# SCH.net
KiCad netlist of a schematic drawn in Altium Designer
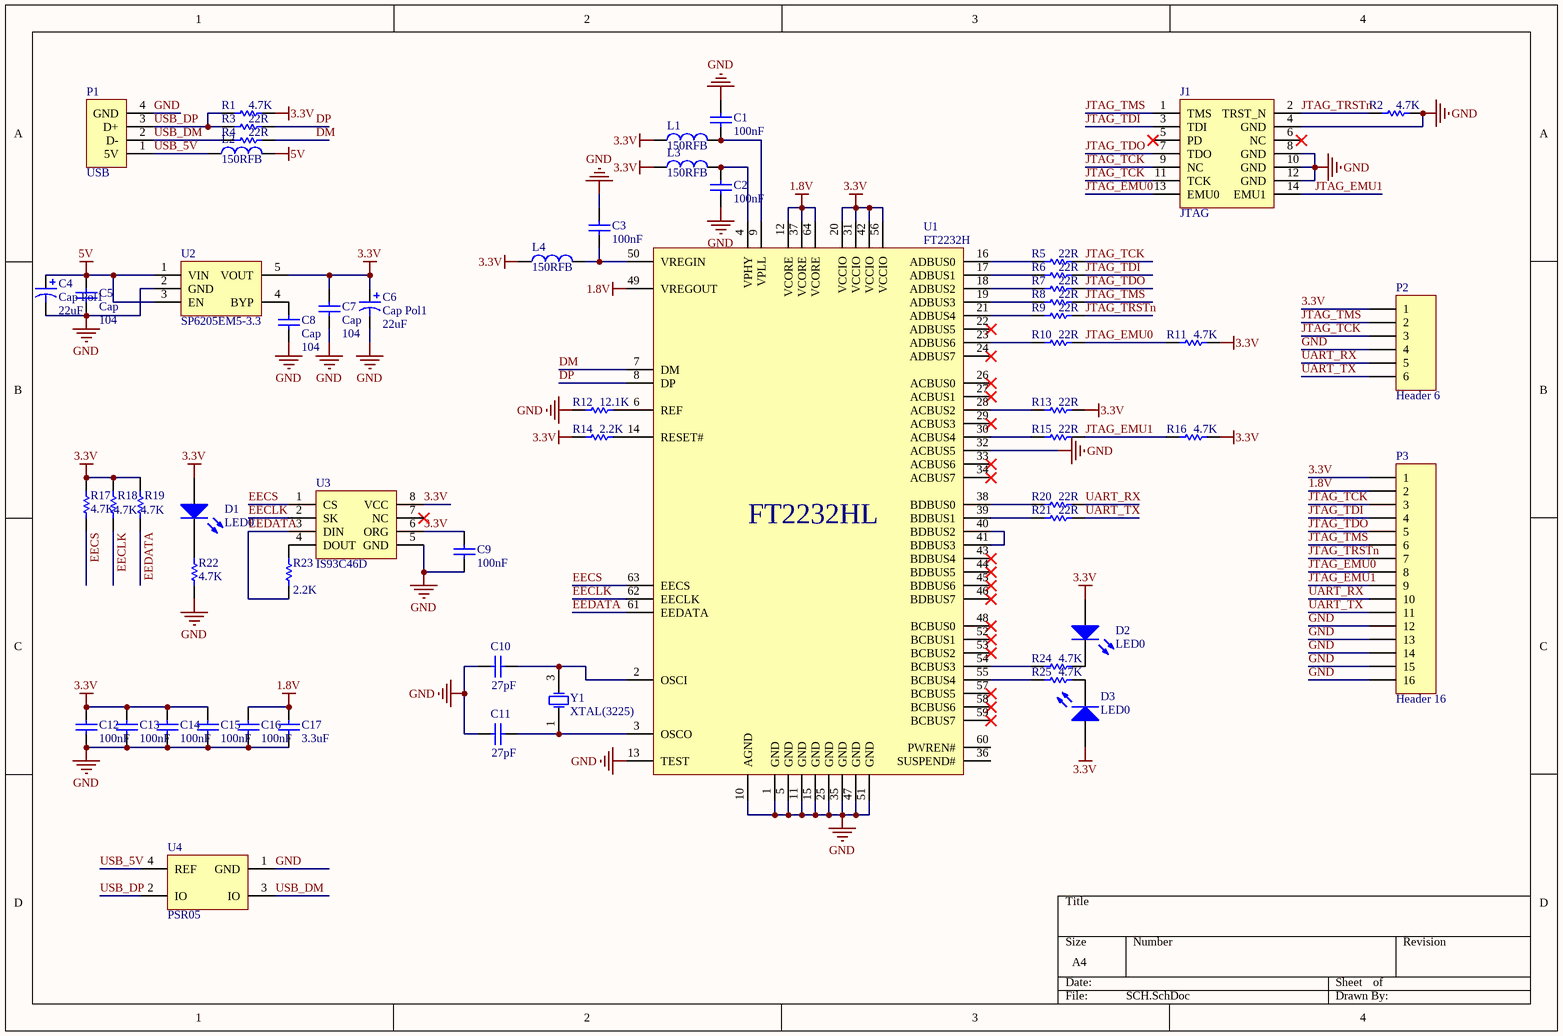
[diagram p0: SCH.SchDoc]

(export (version "E")
  (design (tool "Eeschema 10.0.6"))
  (components
    (comp (ref "C1")
      (value "100nF")
      (footprint "C0603")
      (description "Capacitor")
      (fields (field (name "Comment") "Cap") (field (name "PUBLISHER") "Altium Limited"))
      (libsource (lib "Miscellaneous Devices") (part "Cap"))
    )
    (comp (ref "C2")
      (value "100nF")
      (footprint "C0603")
      (description "Capacitor")
      (fields (field (name "Comment") "Cap") (field (name "PUBLISHER") "Altium Limited"))
      (libsource (lib "Miscellaneous Devices") (part "Cap"))
    )
    (comp (ref "C3")
      (value "100nF")
      (footprint "C0603")
      (description "Capacitor")
      (fields (field (name "Comment") "Cap") (field (name "PUBLISHER") "Altium Limited"))
      (libsource (lib "Miscellaneous Devices") (part "Cap"))
    )
    (comp (ref "C4")
      (value "Cap Pol1")
      (footprint "C0805")
      (description "Polarized Capacitor (Radial)")
      (fields (field (name "ALTIUM_VALUE") "22uF") (field (name "PUBLISHER") "Altium Limited"))
      (libsource (lib "Miscellaneous Devices") (part "Cap Pol1"))
    )
    (comp (ref "C5")
      (value "Cap")
      (footprint "C0603")
      (description "Capacitor")
      (fields (field (name "ALTIUM_VALUE") "104") (field (name "PUBLISHER") "Altium Limited"))
      (libsource (lib "Miscellaneous Devices") (part "Cap"))
    )
    (comp (ref "C6")
      (value "Cap Pol1")
      (footprint "C0805")
      (description "Polarized Capacitor (Radial)")
      (fields (field (name "ALTIUM_VALUE") "22uF") (field (name "PUBLISHER") "Altium Limited"))
      (libsource (lib "Miscellaneous Devices") (part "Cap Pol1"))
    )
    (comp (ref "C7")
      (value "Cap")
      (footprint "C0603")
      (description "Capacitor")
      (fields (field (name "ALTIUM_VALUE") "104") (field (name "PUBLISHER") "Altium Limited"))
      (libsource (lib "Miscellaneous Devices") (part "Cap"))
    )
    (comp (ref "C8")
      (value "Cap")
      (footprint "C0603")
      (description "Capacitor")
      (fields (field (name "ALTIUM_VALUE") "104") (field (name "PUBLISHER") "Altium Limited"))
      (libsource (lib "Miscellaneous Devices") (part "Cap"))
    )
    (comp (ref "C9")
      (value "100nF")
      (footprint "C0603")
      (description "Capacitor")
      (fields (field (name "Comment") "Cap") (field (name "PUBLISHER") "Altium Limited"))
      (libsource (lib "Miscellaneous Devices") (part "Cap"))
    )
    (comp (ref "C10")
      (value "27pF")
      (footprint "C0603")
      (description "Capacitor")
      (fields (field (name "Comment") "Cap") (field (name "PUBLISHER") "Altium Limited"))
      (libsource (lib "Miscellaneous Devices") (part "Cap"))
    )
    (comp (ref "C11")
      (value "27pF")
      (footprint "C0603")
      (description "Capacitor")
      (fields (field (name "Comment") "Cap") (field (name "PUBLISHER") "Altium Limited"))
      (libsource (lib "Miscellaneous Devices") (part "Cap"))
    )
    (comp (ref "C12")
      (value "100nF")
      (footprint "C0603")
      (description "Capacitor")
      (fields (field (name "Comment") "Cap") (field (name "PUBLISHER") "Altium Limited"))
      (libsource (lib "Miscellaneous Devices") (part "Cap"))
    )
    (comp (ref "C13")
      (value "100nF")
      (footprint "C0603")
      (description "Capacitor")
      (fields (field (name "Comment") "Cap") (field (name "PUBLISHER") "Altium Limited"))
      (libsource (lib "Miscellaneous Devices") (part "Cap"))
    )
    (comp (ref "C14")
      (value "100nF")
      (footprint "C0603")
      (description "Capacitor")
      (fields (field (name "Comment") "Cap") (field (name "PUBLISHER") "Altium Limited"))
      (libsource (lib "Miscellaneous Devices") (part "Cap"))
    )
    (comp (ref "C15")
      (value "100nF")
      (footprint "C0603")
      (description "Capacitor")
      (fields (field (name "Comment") "Cap") (field (name "PUBLISHER") "Altium Limited"))
      (libsource (lib "Miscellaneous Devices") (part "Cap"))
    )
    (comp (ref "C16")
      (value "100nF")
      (footprint "C0603")
      (description "Capacitor")
      (fields (field (name "Comment") "Cap") (field (name "PUBLISHER") "Altium Limited"))
      (libsource (lib "Miscellaneous Devices") (part "Cap"))
    )
    (comp (ref "C17")
      (value "3.3uF")
      (footprint "C0603")
      (description "Capacitor")
      (fields (field (name "Comment") "Cap") (field (name "PUBLISHER") "Altium Limited"))
      (libsource (lib "Miscellaneous Devices") (part "Cap"))
    )
    (comp (ref "D1")
      (value "LED0")
      (footprint "0603D")
      (description "Typical INFRARED GaAs LED")
      (fields (field (name "PUBLISHER") "Altium Limited"))
      (libsource (lib "Miscellaneous Devices") (part "LED0"))
    )
    (comp (ref "D2")
      (value "LED0")
      (footprint "0603D")
      (description "Typical INFRARED GaAs LED")
      (fields (field (name "PUBLISHER") "Altium Limited"))
      (libsource (lib "Miscellaneous Devices") (part "LED0"))
    )
    (comp (ref "D3")
      (value "LED0")
      (footprint "0603D")
      (description "Typical INFRARED GaAs LED")
      (fields (field (name "PUBLISHER") "Altium Limited"))
      (libsource (lib "Miscellaneous Devices") (part "LED0"))
    )
    (comp (ref "J1")
      (value "JTAG")
      (footprint "Miscellaneous Connectors:HDR2X7")
      (libsource (lib "schlib_by_wjy") (part "JTAG"))
    )
    (comp (ref "L1")
      (value "150RFB")
      (footprint "r0603")
      (fields (field (name "Comment") "Inductors"))
      (libsource (lib "schlib_by_wjy") (part "Inductors"))
    )
    (comp (ref "L2")
      (value "150RFB")
      (footprint "r0603")
      (fields (field (name "Comment") "Inductors"))
      (libsource (lib "schlib_by_wjy") (part "Inductors"))
    )
    (comp (ref "L3")
      (value "150RFB")
      (footprint "r0603")
      (fields (field (name "Comment") "Inductors"))
      (libsource (lib "schlib_by_wjy") (part "Inductors"))
    )
    (comp (ref "L4")
      (value "150RFB")
      (footprint "r0603")
      (fields (field (name "Comment") "Inductors"))
      (libsource (lib "schlib_by_wjy") (part "Inductors"))
    )
    (comp (ref "P1") (value "USB") (footprint "usb") (libsource (lib "schlib_by_wjy") (part "USB")))
    (comp (ref "P2")
      (value "Header 6")
      (footprint "1.0*6PIN/SMD H")
      (description "Header, 6-Pin")
      (fields (field (name "PUBLISHER") "Altium Limited"))
      (libsource (lib "Miscellaneous Connectors") (part "Header 6"))
    )
    (comp (ref "P3")
      (value "Header 16")
      (footprint "0.5MMFPC_16P")
      (description "Header, 16-Pin")
      (fields (field (name "PUBLISHER") "Altium Limited"))
      (libsource (lib "Miscellaneous Connectors") (part "Header 16"))
    )
    (comp (ref "R1")
      (value "4.7K")
      (footprint "R0603")
      (description "Resistor")
      (fields (field (name "Comment") "Res1") (field (name "PUBLISHER") "Altium Limited"))
      (libsource (lib "Miscellaneous Devices") (part "Res1"))
    )
    (comp (ref "R2")
      (value "4.7K")
      (footprint "R0603")
      (description "Resistor")
      (fields (field (name "Comment") "Res1") (field (name "PUBLISHER") "Altium Limited"))
      (libsource (lib "Miscellaneous Devices") (part "Res1"))
    )
    (comp (ref "R3")
      (value "22R")
      (footprint "R0603")
      (description "Resistor")
      (fields (field (name "Comment") "Res1") (field (name "PUBLISHER") "Altium Limited"))
      (libsource (lib "Miscellaneous Devices") (part "Res1"))
    )
    (comp (ref "R4")
      (value "22R")
      (footprint "R0603")
      (description "Resistor")
      (fields (field (name "Comment") "Res1") (field (name "PUBLISHER") "Altium Limited"))
      (libsource (lib "Miscellaneous Devices") (part "Res1"))
    )
    (comp (ref "R5")
      (value "22R")
      (footprint "R0603")
      (description "Resistor")
      (fields (field (name "Comment") "Res1") (field (name "PUBLISHER") "Altium Limited"))
      (libsource (lib "Miscellaneous Devices") (part "Res1"))
    )
    (comp (ref "R6")
      (value "22R")
      (footprint "R0603")
      (description "Resistor")
      (fields (field (name "Comment") "Res1") (field (name "PUBLISHER") "Altium Limited"))
      (libsource (lib "Miscellaneous Devices") (part "Res1"))
    )
    (comp (ref "R7")
      (value "22R")
      (footprint "R0603")
      (description "Resistor")
      (fields (field (name "Comment") "Res1") (field (name "PUBLISHER") "Altium Limited"))
      (libsource (lib "Miscellaneous Devices") (part "Res1"))
    )
    (comp (ref "R8")
      (value "22R")
      (footprint "R0603")
      (description "Resistor")
      (fields (field (name "Comment") "Res1") (field (name "PUBLISHER") "Altium Limited"))
      (libsource (lib "Miscellaneous Devices") (part "Res1"))
    )
    (comp (ref "R9")
      (value "22R")
      (footprint "R0603")
      (description "Resistor")
      (fields (field (name "Comment") "Res1") (field (name "PUBLISHER") "Altium Limited"))
      (libsource (lib "Miscellaneous Devices") (part "Res1"))
    )
    (comp (ref "R10")
      (value "22R")
      (footprint "R0603")
      (description "Resistor")
      (fields (field (name "Comment") "Res1") (field (name "PUBLISHER") "Altium Limited"))
      (libsource (lib "Miscellaneous Devices") (part "Res1"))
    )
    (comp (ref "R11")
      (value "4.7K")
      (footprint "R0603")
      (description "Resistor")
      (fields (field (name "Comment") "Res1") (field (name "PUBLISHER") "Altium Limited"))
      (libsource (lib "Miscellaneous Devices") (part "Res1"))
    )
    (comp (ref "R12")
      (value "12.1K")
      (footprint "R0603")
      (description "Resistor")
      (fields (field (name "Comment") "Res1") (field (name "PUBLISHER") "Altium Limited"))
      (libsource (lib "Miscellaneous Devices") (part "Res1"))
    )
    (comp (ref "R13")
      (value "22R")
      (footprint "R0603")
      (description "Resistor")
      (fields (field (name "Comment") "Res1") (field (name "PUBLISHER") "Altium Limited"))
      (libsource (lib "Miscellaneous Devices") (part "Res1"))
    )
    (comp (ref "R14")
      (value "2.2K")
      (footprint "R0603")
      (description "Resistor")
      (fields (field (name "Comment") "Res1") (field (name "PUBLISHER") "Altium Limited"))
      (libsource (lib "Miscellaneous Devices") (part "Res1"))
    )
    (comp (ref "R15")
      (value "22R")
      (footprint "R0603")
      (description "Resistor")
      (fields (field (name "Comment") "Res1") (field (name "PUBLISHER") "Altium Limited"))
      (libsource (lib "Miscellaneous Devices") (part "Res1"))
    )
    (comp (ref "R16")
      (value "4.7K")
      (footprint "R0603")
      (description "Resistor")
      (fields (field (name "Comment") "Res1") (field (name "PUBLISHER") "Altium Limited"))
      (libsource (lib "Miscellaneous Devices") (part "Res1"))
    )
    (comp (ref "R17")
      (value "4.7K")
      (footprint "R0603")
      (description "Resistor")
      (fields (field (name "Comment") "Res1") (field (name "PUBLISHER") "Altium Limited"))
      (libsource (lib "Miscellaneous Devices") (part "Res1"))
    )
    (comp (ref "R18")
      (value "4.7K")
      (footprint "R0603")
      (description "Resistor")
      (fields (field (name "Comment") "Res1") (field (name "PUBLISHER") "Altium Limited"))
      (libsource (lib "Miscellaneous Devices") (part "Res1"))
    )
    (comp (ref "R19")
      (value "4.7K")
      (footprint "R0603")
      (description "Resistor")
      (fields (field (name "Comment") "Res1") (field (name "PUBLISHER") "Altium Limited"))
      (libsource (lib "Miscellaneous Devices") (part "Res1"))
    )
    (comp (ref "R20")
      (value "22R")
      (footprint "R0603")
      (description "Resistor")
      (fields (field (name "Comment") "Res1") (field (name "PUBLISHER") "Altium Limited"))
      (libsource (lib "Miscellaneous Devices") (part "Res1"))
    )
    (comp (ref "R21")
      (value "22R")
      (footprint "R0603")
      (description "Resistor")
      (fields (field (name "Comment") "Res1") (field (name "PUBLISHER") "Altium Limited"))
      (libsource (lib "Miscellaneous Devices") (part "Res1"))
    )
    (comp (ref "R22")
      (value "4.7K")
      (footprint "R0603")
      (description "Resistor")
      (fields (field (name "Comment") "Res1") (field (name "PUBLISHER") "Altium Limited"))
      (libsource (lib "Miscellaneous Devices") (part "Res1"))
    )
    (comp (ref "R23")
      (value "2.2K")
      (footprint "R0603")
      (description "Resistor")
      (fields (field (name "Comment") "Res1") (field (name "PUBLISHER") "Altium Limited"))
      (libsource (lib "Miscellaneous Devices") (part "Res1"))
    )
    (comp (ref "R24")
      (value "4.7K")
      (footprint "R0603")
      (description "Resistor")
      (fields (field (name "Comment") "Res1") (field (name "PUBLISHER") "Altium Limited"))
      (libsource (lib "Miscellaneous Devices") (part "Res1"))
    )
    (comp (ref "R25")
      (value "4.7K")
      (footprint "R0603")
      (description "Resistor")
      (fields (field (name "Comment") "Res1") (field (name "PUBLISHER") "Altium Limited"))
      (libsource (lib "Miscellaneous Devices") (part "Res1"))
    )
    (comp (ref "U1") (value "FT2232H") (footprint "LQFP64") (libsource (lib "Schlib") (part "FT2232H")))
    (comp (ref "U2")
      (value "SP6205EM5-3.3")
      (footprint "SOT-23-5")
      (description "AD3330")
      (libsource (lib "四旋翼") (part "SP6205"))
    )
    (comp (ref "U3") (value "IS93C46D") (footprint "SO8") (libsource (lib "Schlib") (part "IS93C46D")))
    (comp (ref "U4") (value "PSR05") (footprint "SOT143") (libsource (lib "Schlib") (part "PSR05")))
    (comp (ref "Y1")
      (value "XTAL(3225)")
      (footprint "Y3225")
      (description "Crystal Oscillator")
      (fields (field (name "PUBLISHER") "Altium Limited"))
      (libsource (lib "schlib_by_wjy") (part "XTAL(3225)"))
    )
  )
  (nets
    (net (code "1") (name "/DM") (class "Default")
      (node (ref "R4") (pin "1") (pinfunction "1_1") (pintype "passive"))
      (node (ref "U1") (pin "7") (pinfunction "DM_7") (pintype "passive"))
    )
    (net (code "2") (name "/DP") (class "Default")
      (node (ref "R3") (pin "1") (pinfunction "1_1") (pintype "passive"))
      (node (ref "U1") (pin "8") (pinfunction "DP_8") (pintype "passive"))
    )
    (net (code "3") (name "/EECLK") (class "Default")
      (node (ref "R18") (pin "1") (pinfunction "1_1") (pintype "passive"))
      (node (ref "U1") (pin "62") (pinfunction "EECLK_62") (pintype "passive"))
      (node (ref "U3") (pin "2") (pinfunction "SK_2") (pintype "passive"))
    )
    (net (code "4") (name "/EECS") (class "Default")
      (node (ref "R17") (pin "2") (pinfunction "2_2") (pintype "passive"))
      (node (ref "U1") (pin "63") (pinfunction "EECS_63") (pintype "passive"))
      (node (ref "U3") (pin "1") (pinfunction "CS_1") (pintype "passive"))
    )
    (net (code "5") (name "/EEDATA") (class "Default")
      (node (ref "R19") (pin "1") (pinfunction "1_1") (pintype "passive"))
      (node (ref "R23") (pin "1") (pinfunction "1_1") (pintype "passive"))
      (node (ref "U1") (pin "61") (pinfunction "EEDATA_61") (pintype "passive"))
      (node (ref "U3") (pin "3") (pinfunction "DIN_3") (pintype "passive"))
    )
    (net (code "6") (name "/JTAG_EMU0") (class "Default")
      (node (ref "J1") (pin "13") (pinfunction "EMU0_13") (pintype "passive"))
      (node (ref "P3") (pin "8") (pinfunction "8_8") (pintype "passive"))
      (node (ref "R10") (pin "1") (pinfunction "1_1") (pintype "passive"))
      (node (ref "R11") (pin "2") (pinfunction "2_2") (pintype "passive"))
    )
    (net (code "7") (name "/JTAG_EMU1") (class "Default")
      (node (ref "J1") (pin "14") (pinfunction "EMU1_14") (pintype "passive"))
      (node (ref "P3") (pin "9") (pinfunction "9_9") (pintype "passive"))
      (node (ref "R15") (pin "1") (pinfunction "1_1") (pintype "passive"))
      (node (ref "R16") (pin "2") (pinfunction "2_2") (pintype "passive"))
    )
    (net (code "8") (name "/JTAG_TCK") (class "Default")
      (node (ref "J1") (pin "11") (pinfunction "TCK_11") (pintype "passive"))
      (node (ref "J1") (pin "9") (pinfunction "NC_9") (pintype "passive"))
      (node (ref "P2") (pin "3") (pinfunction "3_3") (pintype "passive"))
      (node (ref "P3") (pin "3") (pinfunction "3_3") (pintype "passive"))
      (node (ref "R5") (pin "1") (pinfunction "1_1") (pintype "passive"))
    )
    (net (code "9") (name "/JTAG_TDI") (class "Default")
      (node (ref "J1") (pin "3") (pinfunction "TDI_3") (pintype "passive"))
      (node (ref "P3") (pin "4") (pinfunction "4_4") (pintype "passive"))
      (node (ref "R6") (pin "1") (pinfunction "1_1") (pintype "passive"))
    )
    (net (code "10") (name "/JTAG_TDO") (class "Default")
      (node (ref "J1") (pin "7") (pinfunction "TDO_7") (pintype "passive"))
      (node (ref "P3") (pin "5") (pinfunction "5_5") (pintype "passive"))
      (node (ref "R7") (pin "1") (pinfunction "1_1") (pintype "passive"))
    )
    (net (code "11") (name "/JTAG_TMS") (class "Default")
      (node (ref "J1") (pin "1") (pinfunction "TMS_1") (pintype "passive"))
      (node (ref "P2") (pin "2") (pinfunction "2_2") (pintype "passive"))
      (node (ref "P3") (pin "6") (pinfunction "6_6") (pintype "passive"))
      (node (ref "R8") (pin "1") (pinfunction "1_1") (pintype "passive"))
    )
    (net (code "12") (name "/JTAG_TRSTn") (class "Default")
      (node (ref "J1") (pin "2") (pinfunction "TRST_N_2") (pintype "passive"))
      (node (ref "P3") (pin "7") (pinfunction "7_7") (pintype "passive"))
      (node (ref "R2") (pin "2") (pinfunction "2_2") (pintype "passive"))
      (node (ref "R9") (pin "1") (pinfunction "1_1") (pintype "passive"))
    )
    (net (code "13") (name "/UART_RX") (class "Default")
      (node (ref "P2") (pin "5") (pinfunction "5_5") (pintype "passive"))
      (node (ref "P3") (pin "10") (pinfunction "10_10") (pintype "passive"))
      (node (ref "R20") (pin "1") (pinfunction "1_1") (pintype "passive"))
    )
    (net (code "14") (name "/UART_TX") (class "Default")
      (node (ref "P2") (pin "6") (pinfunction "6_6") (pintype "passive"))
      (node (ref "P3") (pin "11") (pinfunction "11_11") (pintype "passive"))
      (node (ref "R21") (pin "1") (pinfunction "1_1") (pintype "passive"))
    )
    (net (code "15") (name "/USB_5V") (class "Default")
      (node (ref "L2") (pin "1") (pinfunction "1_1") (pintype "passive"))
      (node (ref "P1") (pin "1") (pinfunction "5V_1") (pintype "passive"))
      (node (ref "U4") (pin "4") (pinfunction "REF_4") (pintype "passive"))
    )
    (net (code "16") (name "/USB_DM") (class "Default")
      (node (ref "P1") (pin "2") (pinfunction "D-_2") (pintype "passive"))
      (node (ref "R4") (pin "2") (pinfunction "2_2") (pintype "passive"))
      (node (ref "U4") (pin "3") (pinfunction "IO_3") (pintype "passive"))
    )
    (net (code "17") (name "/USB_DP") (class "Default")
      (node (ref "P1") (pin "3") (pinfunction "D+_3") (pintype "passive"))
      (node (ref "R1") (pin "2") (pinfunction "2_2") (pintype "passive"))
      (node (ref "R3") (pin "2") (pinfunction "2_2") (pintype "passive"))
      (node (ref "U4") (pin "2") (pinfunction "IO_2") (pintype "passive"))
    )
    (net (code "18") (name "1.8V") (class "Default")
      (node (ref "C16") (pin "1") (pinfunction "1_1") (pintype "passive"))
      (node (ref "C17") (pin "1") (pinfunction "1_1") (pintype "passive"))
      (node (ref "P3") (pin "2") (pinfunction "2_2") (pintype "passive"))
      (node (ref "U1") (pin "12") (pinfunction "VCORE_12") (pintype "passive"))
      (node (ref "U1") (pin "37") (pinfunction "VCORE_37") (pintype "passive"))
      (node (ref "U1") (pin "49") (pinfunction "VREGOUT_49") (pintype "passive"))
      (node (ref "U1") (pin "64") (pinfunction "VCORE_64") (pintype "passive"))
    )
    (net (code "19") (name "3.3V") (class "Default")
      (node (ref "C12") (pin "1") (pinfunction "1_1") (pintype "passive"))
      (node (ref "C13") (pin "1") (pinfunction "1_1") (pintype "passive"))
      (node (ref "C14") (pin "1") (pinfunction "1_1") (pintype "passive"))
      (node (ref "C15") (pin "1") (pinfunction "1_1") (pintype "passive"))
      (node (ref "C6") (pin "1") (pinfunction "1_1") (pintype "passive"))
      (node (ref "C7") (pin "2") (pinfunction "2_2") (pintype "passive"))
      (node (ref "C9") (pin "1") (pinfunction "1_1") (pintype "passive"))
      (node (ref "D1") (pin "1") (pinfunction "A_1") (pintype "passive"))
      (node (ref "D2") (pin "1") (pinfunction "A_1") (pintype "passive"))
      (node (ref "D3") (pin "1") (pinfunction "A_1") (pintype "passive"))
      (node (ref "L1") (pin "1") (pinfunction "1_1") (pintype "passive"))
      (node (ref "L3") (pin "1") (pinfunction "1_1") (pintype "passive"))
      (node (ref "L4") (pin "1") (pinfunction "1_1") (pintype "passive"))
      (node (ref "P2") (pin "1") (pinfunction "1_1") (pintype "passive"))
      (node (ref "P3") (pin "1") (pinfunction "1_1") (pintype "passive"))
      (node (ref "R1") (pin "1") (pinfunction "1_1") (pintype "passive"))
      (node (ref "R11") (pin "1") (pinfunction "1_1") (pintype "passive"))
      (node (ref "R13") (pin "1") (pinfunction "1_1") (pintype "passive"))
      (node (ref "R14") (pin "2") (pinfunction "2_2") (pintype "passive"))
      (node (ref "R16") (pin "1") (pinfunction "1_1") (pintype "passive"))
      (node (ref "R17") (pin "1") (pinfunction "1_1") (pintype "passive"))
      (node (ref "R18") (pin "2") (pinfunction "2_2") (pintype "passive"))
      (node (ref "R19") (pin "2") (pinfunction "2_2") (pintype "passive"))
      (node (ref "U1") (pin "20") (pinfunction "VCCIO_20") (pintype "passive"))
      (node (ref "U1") (pin "31") (pinfunction "VCCIO_31") (pintype "passive"))
      (node (ref "U1") (pin "42") (pinfunction "VCCIO_42") (pintype "passive"))
      (node (ref "U1") (pin "56") (pinfunction "VCCIO_56") (pintype "passive"))
      (node (ref "U2") (pin "5") (pinfunction "VOUT_5") (pintype "passive"))
      (node (ref "U3") (pin "6") (pinfunction "ORG_6") (pintype "passive"))
      (node (ref "U3") (pin "8") (pinfunction "VCC_8") (pintype "passive"))
    )
    (net (code "20") (name "5V") (class "Default")
      (node (ref "C4") (pin "1") (pinfunction "1_1") (pintype "passive"))
      (node (ref "C5") (pin "2") (pinfunction "2_2") (pintype "passive"))
      (node (ref "L2") (pin "2") (pinfunction "2_2") (pintype "passive"))
      (node (ref "U2") (pin "1") (pinfunction "VIN_1") (pintype "passive"))
      (node (ref "U2") (pin "3") (pinfunction "EN_3") (pintype "passive"))
    )
    (net (code "21") (name "GND") (class "Default")
      (node (ref "C1") (pin "1") (pinfunction "1_1") (pintype "passive"))
      (node (ref "C10") (pin "2") (pinfunction "2_2") (pintype "passive"))
      (node (ref "C11") (pin "2") (pinfunction "2_2") (pintype "passive"))
      (node (ref "C12") (pin "2") (pinfunction "2_2") (pintype "passive"))
      (node (ref "C13") (pin "2") (pinfunction "2_2") (pintype "passive"))
      (node (ref "C14") (pin "2") (pinfunction "2_2") (pintype "passive"))
      (node (ref "C15") (pin "2") (pinfunction "2_2") (pintype "passive"))
      (node (ref "C16") (pin "2") (pinfunction "2_2") (pintype "passive"))
      (node (ref "C17") (pin "2") (pinfunction "2_2") (pintype "passive"))
      (node (ref "C2") (pin "2") (pinfunction "2_2") (pintype "passive"))
      (node (ref "C3") (pin "1") (pinfunction "1_1") (pintype "passive"))
      (node (ref "C4") (pin "2") (pinfunction "2_2") (pintype "passive"))
      (node (ref "C5") (pin "1") (pinfunction "1_1") (pintype "passive"))
      (node (ref "C6") (pin "2") (pinfunction "2_2") (pintype "passive"))
      (node (ref "C7") (pin "1") (pinfunction "1_1") (pintype "passive"))
      (node (ref "C8") (pin "1") (pinfunction "1_1") (pintype "passive"))
      (node (ref "C9") (pin "2") (pinfunction "2_2") (pintype "passive"))
      (node (ref "J1") (pin "10") (pinfunction "GND_10") (pintype "passive"))
      (node (ref "J1") (pin "12") (pinfunction "GND_12") (pintype "passive"))
      (node (ref "J1") (pin "4") (pinfunction "GND_4") (pintype "passive"))
      (node (ref "J1") (pin "8") (pinfunction "GND_8") (pintype "passive"))
      (node (ref "P1") (pin "4") (pinfunction "GND_4") (pintype "passive"))
      (node (ref "P2") (pin "4") (pinfunction "4_4") (pintype "passive"))
      (node (ref "P3") (pin "12") (pinfunction "12_12") (pintype "passive"))
      (node (ref "P3") (pin "13") (pinfunction "13_13") (pintype "passive"))
      (node (ref "P3") (pin "14") (pinfunction "14_14") (pintype "passive"))
      (node (ref "P3") (pin "15") (pinfunction "15_15") (pintype "passive"))
      (node (ref "P3") (pin "16") (pinfunction "16_16") (pintype "passive"))
      (node (ref "R12") (pin "2") (pinfunction "2_2") (pintype "passive"))
      (node (ref "R2") (pin "1") (pinfunction "1_1") (pintype "passive"))
      (node (ref "R22") (pin "2") (pinfunction "2_2") (pintype "passive"))
      (node (ref "U1") (pin "1") (pinfunction "GND_1") (pintype "passive"))
      (node (ref "U1") (pin "10") (pinfunction "AGND_10") (pintype "passive"))
      (node (ref "U1") (pin "11") (pinfunction "GND_11") (pintype "passive"))
      (node (ref "U1") (pin "13") (pinfunction "TEST_13") (pintype "passive"))
      (node (ref "U1") (pin "15") (pinfunction "GND_15") (pintype "passive"))
      (node (ref "U1") (pin "25") (pinfunction "GND_25") (pintype "passive"))
      (node (ref "U1") (pin "32") (pinfunction "ACBUS5_32") (pintype "passive"))
      (node (ref "U1") (pin "35") (pinfunction "GND_35") (pintype "passive"))
      (node (ref "U1") (pin "47") (pinfunction "GND_47") (pintype "passive"))
      (node (ref "U1") (pin "5") (pinfunction "GND_5") (pintype "passive"))
      (node (ref "U1") (pin "51") (pinfunction "GND_51") (pintype "passive"))
      (node (ref "U2") (pin "2") (pinfunction "GND_2") (pintype "passive"))
      (node (ref "U3") (pin "5") (pinfunction "GND_5") (pintype "passive"))
      (node (ref "U4") (pin "1") (pinfunction "GND_1") (pintype "passive"))
    )
    (net (code "22") (name "Net-(D1-K)") (class "Default")
      (node (ref "D1") (pin "2") (pinfunction "K_2") (pintype "passive"))
      (node (ref "R22") (pin "1") (pinfunction "1_1") (pintype "passive"))
    )
    (net (code "23") (name "Net-(D2-K)") (class "Default")
      (node (ref "D2") (pin "2") (pinfunction "K_2") (pintype "passive"))
      (node (ref "R24") (pin "1") (pinfunction "1_1") (pintype "passive"))
    )
    (net (code "24") (name "Net-(D3-K)") (class "Default")
      (node (ref "D3") (pin "2") (pinfunction "K_2") (pintype "passive"))
      (node (ref "R25") (pin "1") (pinfunction "1_1") (pintype "passive"))
    )
    (net (code "25") (name "Net-(U1-ACBUS2)") (class "Default")
      (node (ref "R13") (pin "2") (pinfunction "2_2") (pintype "passive"))
      (node (ref "U1") (pin "28") (pinfunction "ACBUS2_28") (pintype "passive"))
    )
    (net (code "26") (name "Net-(U1-ACBUS4)") (class "Default")
      (node (ref "R15") (pin "2") (pinfunction "2_2") (pintype "passive"))
      (node (ref "U1") (pin "30") (pinfunction "ACBUS4_30") (pintype "passive"))
    )
    (net (code "27") (name "Net-(U1-ADBUS0)") (class "Default")
      (node (ref "R5") (pin "2") (pinfunction "2_2") (pintype "passive"))
      (node (ref "U1") (pin "16") (pinfunction "ADBUS0_16") (pintype "passive"))
    )
    (net (code "28") (name "Net-(U1-ADBUS1)") (class "Default")
      (node (ref "R6") (pin "2") (pinfunction "2_2") (pintype "passive"))
      (node (ref "U1") (pin "17") (pinfunction "ADBUS1_17") (pintype "passive"))
    )
    (net (code "29") (name "Net-(U1-ADBUS2)") (class "Default")
      (node (ref "R7") (pin "2") (pinfunction "2_2") (pintype "passive"))
      (node (ref "U1") (pin "18") (pinfunction "ADBUS2_18") (pintype "passive"))
    )
    (net (code "30") (name "Net-(U1-ADBUS3)") (class "Default")
      (node (ref "R8") (pin "2") (pinfunction "2_2") (pintype "passive"))
      (node (ref "U1") (pin "19") (pinfunction "ADBUS3_19") (pintype "passive"))
    )
    (net (code "31") (name "Net-(U1-ADBUS4)") (class "Default")
      (node (ref "R9") (pin "2") (pinfunction "2_2") (pintype "passive"))
      (node (ref "U1") (pin "21") (pinfunction "ADBUS4_21") (pintype "passive"))
    )
    (net (code "32") (name "Net-(U1-ADBUS6)") (class "Default")
      (node (ref "R10") (pin "2") (pinfunction "2_2") (pintype "passive"))
      (node (ref "U1") (pin "23") (pinfunction "ADBUS6_23") (pintype "passive"))
    )
    (net (code "33") (name "Net-(U1-BCBUS3)") (class "Default")
      (node (ref "R24") (pin "2") (pinfunction "2_2") (pintype "passive"))
      (node (ref "U1") (pin "54") (pinfunction "BCBUS3_54") (pintype "passive"))
    )
    (net (code "34") (name "Net-(U1-BCBUS4)") (class "Default")
      (node (ref "R25") (pin "2") (pinfunction "2_2") (pintype "passive"))
      (node (ref "U1") (pin "55") (pinfunction "BCBUS4_55") (pintype "passive"))
    )
    (net (code "35") (name "Net-(U1-BDBUS0)") (class "Default")
      (node (ref "R20") (pin "2") (pinfunction "2_2") (pintype "passive"))
      (node (ref "U1") (pin "38") (pinfunction "BDBUS0_38") (pintype "passive"))
    )
    (net (code "36") (name "Net-(U1-BDBUS1)") (class "Default")
      (node (ref "R21") (pin "2") (pinfunction "2_2") (pintype "passive"))
      (node (ref "U1") (pin "39") (pinfunction "BDBUS1_39") (pintype "passive"))
    )
    (net (code "37") (name "Net-(U1-BDBUS2)") (class "Default")
      (node (ref "U1") (pin "40") (pinfunction "BDBUS2_40") (pintype "passive"))
      (node (ref "U1") (pin "41") (pinfunction "BDBUS3_41") (pintype "passive"))
    )
    (net (code "38") (name "Net-(U1-OSCI)") (class "Default")
      (node (ref "C10") (pin "1") (pinfunction "1_1") (pintype "passive"))
      (node (ref "U1") (pin "2") (pinfunction "OSCI_2") (pintype "passive"))
      (node (ref "Y1") (pin "3") (pinfunction "OSC2_3") (pintype "passive"))
    )
    (net (code "39") (name "Net-(U1-OSCO)") (class "Default")
      (node (ref "C11") (pin "1") (pinfunction "1_1") (pintype "passive"))
      (node (ref "U1") (pin "3") (pinfunction "OSCO_3") (pintype "passive"))
      (node (ref "Y1") (pin "1") (pinfunction "OSC1_1") (pintype "passive"))
    )
    (net (code "40") (name "Net-(U1-REF)") (class "Default")
      (node (ref "R12") (pin "1") (pinfunction "1_1") (pintype "passive"))
      (node (ref "U1") (pin "6") (pinfunction "REF_6") (pintype "passive"))
    )
    (net (code "41") (name "Net-(U1-RESET#)") (class "Default")
      (node (ref "R14") (pin "1") (pinfunction "1_1") (pintype "passive"))
      (node (ref "U1") (pin "14") (pinfunction "RESET#_14") (pintype "passive"))
    )
    (net (code "42") (name "Net-(U1-VPHY)") (class "Default")
      (node (ref "C2") (pin "1") (pinfunction "1_1") (pintype "passive"))
      (node (ref "L3") (pin "2") (pinfunction "2_2") (pintype "passive"))
      (node (ref "U1") (pin "4") (pinfunction "VPHY_4") (pintype "passive"))
    )
    (net (code "43") (name "Net-(U1-VPLL)") (class "Default")
      (node (ref "C1") (pin "2") (pinfunction "2_2") (pintype "passive"))
      (node (ref "L1") (pin "2") (pinfunction "2_2") (pintype "passive"))
      (node (ref "U1") (pin "9") (pinfunction "VPLL_9") (pintype "passive"))
    )
    (net (code "44") (name "Net-(U1-VREGIN)") (class "Default")
      (node (ref "C3") (pin "2") (pinfunction "2_2") (pintype "passive"))
      (node (ref "L4") (pin "2") (pinfunction "2_2") (pintype "passive"))
      (node (ref "U1") (pin "50") (pinfunction "VREGIN_50") (pintype "passive"))
    )
    (net (code "45") (name "Net-(U2-BYP)") (class "Default")
      (node (ref "C8") (pin "2") (pinfunction "2_2") (pintype "passive"))
      (node (ref "U2") (pin "4") (pinfunction "BYP_4") (pintype "passive"))
    )
    (net (code "46") (name "Net-(U3-DOUT)") (class "Default")
      (node (ref "R23") (pin "2") (pinfunction "2_2") (pintype "passive"))
      (node (ref "U3") (pin "4") (pinfunction "DOUT_4") (pintype "passive"))
    )
    (net (code "47") (name "unconnected-(J1-NC-Pad6)") (class "Default")
      (node (ref "J1") (pin "6") (pinfunction "NC_6") (pintype "passive+no_connect"))
    )
    (net (code "48") (name "unconnected-(J1-PD-Pad5)") (class "Default")
      (node (ref "J1") (pin "5") (pinfunction "PD_5") (pintype "passive+no_connect"))
    )
    (net (code "49") (name "unconnected-(U1-ACBUS0-Pad26)") (class "Default")
      (node (ref "U1") (pin "26") (pinfunction "ACBUS0_26") (pintype "passive+no_connect"))
    )
    (net (code "50") (name "unconnected-(U1-ACBUS1-Pad27)") (class "Default")
      (node (ref "U1") (pin "27") (pinfunction "ACBUS1_27") (pintype "passive+no_connect"))
    )
    (net (code "51") (name "unconnected-(U1-ACBUS3-Pad29)") (class "Default")
      (node (ref "U1") (pin "29") (pinfunction "ACBUS3_29") (pintype "passive+no_connect"))
    )
    (net (code "52") (name "unconnected-(U1-ACBUS6-Pad33)") (class "Default")
      (node (ref "U1") (pin "33") (pinfunction "ACBUS6_33") (pintype "passive+no_connect"))
    )
    (net (code "53") (name "unconnected-(U1-ACBUS7-Pad34)") (class "Default")
      (node (ref "U1") (pin "34") (pinfunction "ACBUS7_34") (pintype "passive+no_connect"))
    )
    (net (code "54") (name "unconnected-(U1-ADBUS5-Pad22)") (class "Default")
      (node (ref "U1") (pin "22") (pinfunction "ADBUS5_22") (pintype "passive+no_connect"))
    )
    (net (code "55") (name "unconnected-(U1-ADBUS7-Pad24)") (class "Default")
      (node (ref "U1") (pin "24") (pinfunction "ADBUS7_24") (pintype "passive+no_connect"))
    )
    (net (code "56") (name "unconnected-(U1-BCBUS0-Pad48)") (class "Default")
      (node (ref "U1") (pin "48") (pinfunction "BCBUS0_48") (pintype "passive+no_connect"))
    )
    (net (code "57") (name "unconnected-(U1-BCBUS1-Pad52)") (class "Default")
      (node (ref "U1") (pin "52") (pinfunction "BCBUS1_52") (pintype "passive+no_connect"))
    )
    (net (code "58") (name "unconnected-(U1-BCBUS2-Pad53)") (class "Default")
      (node (ref "U1") (pin "53") (pinfunction "BCBUS2_53") (pintype "passive+no_connect"))
    )
    (net (code "59") (name "unconnected-(U1-BCBUS5-Pad57)") (class "Default")
      (node (ref "U1") (pin "57") (pinfunction "BCBUS5_57") (pintype "passive+no_connect"))
    )
    (net (code "60") (name "unconnected-(U1-BCBUS6-Pad58)") (class "Default")
      (node (ref "U1") (pin "58") (pinfunction "BCBUS6_58") (pintype "passive+no_connect"))
    )
    (net (code "61") (name "unconnected-(U1-BCBUS7-Pad59)") (class "Default")
      (node (ref "U1") (pin "59") (pinfunction "BCBUS7_59") (pintype "passive+no_connect"))
    )
    (net (code "62") (name "unconnected-(U1-BDBUS4-Pad43)") (class "Default")
      (node (ref "U1") (pin "43") (pinfunction "BDBUS4_43") (pintype "passive+no_connect"))
    )
    (net (code "63") (name "unconnected-(U1-BDBUS5-Pad44)") (class "Default")
      (node (ref "U1") (pin "44") (pinfunction "BDBUS5_44") (pintype "passive+no_connect"))
    )
    (net (code "64") (name "unconnected-(U1-BDBUS6-Pad45)") (class "Default")
      (node (ref "U1") (pin "45") (pinfunction "BDBUS6_45") (pintype "passive+no_connect"))
    )
    (net (code "65") (name "unconnected-(U1-BDBUS7-Pad46)") (class "Default")
      (node (ref "U1") (pin "46") (pinfunction "BDBUS7_46") (pintype "passive+no_connect"))
    )
    (net (code "66") (name "unconnected-(U1-PWREN#-Pad60)") (class "Default")
      (node (ref "U1") (pin "60") (pinfunction "PWREN#_60") (pintype "passive"))
    )
    (net (code "67") (name "unconnected-(U1-SUSPEND#-Pad36)") (class "Default")
      (node (ref "U1") (pin "36") (pinfunction "SUSPEND#_36") (pintype "passive"))
    )
    (net (code "68") (name "unconnected-(U3-NC-Pad7)") (class "Default")
      (node (ref "U3") (pin "7") (pinfunction "NC_7") (pintype "passive+no_connect"))
    )
  )
)
